# E22_TTL_RS232_v0_2_-20200615.net
KiCad netlist of a schematic drawn in Altium Designer
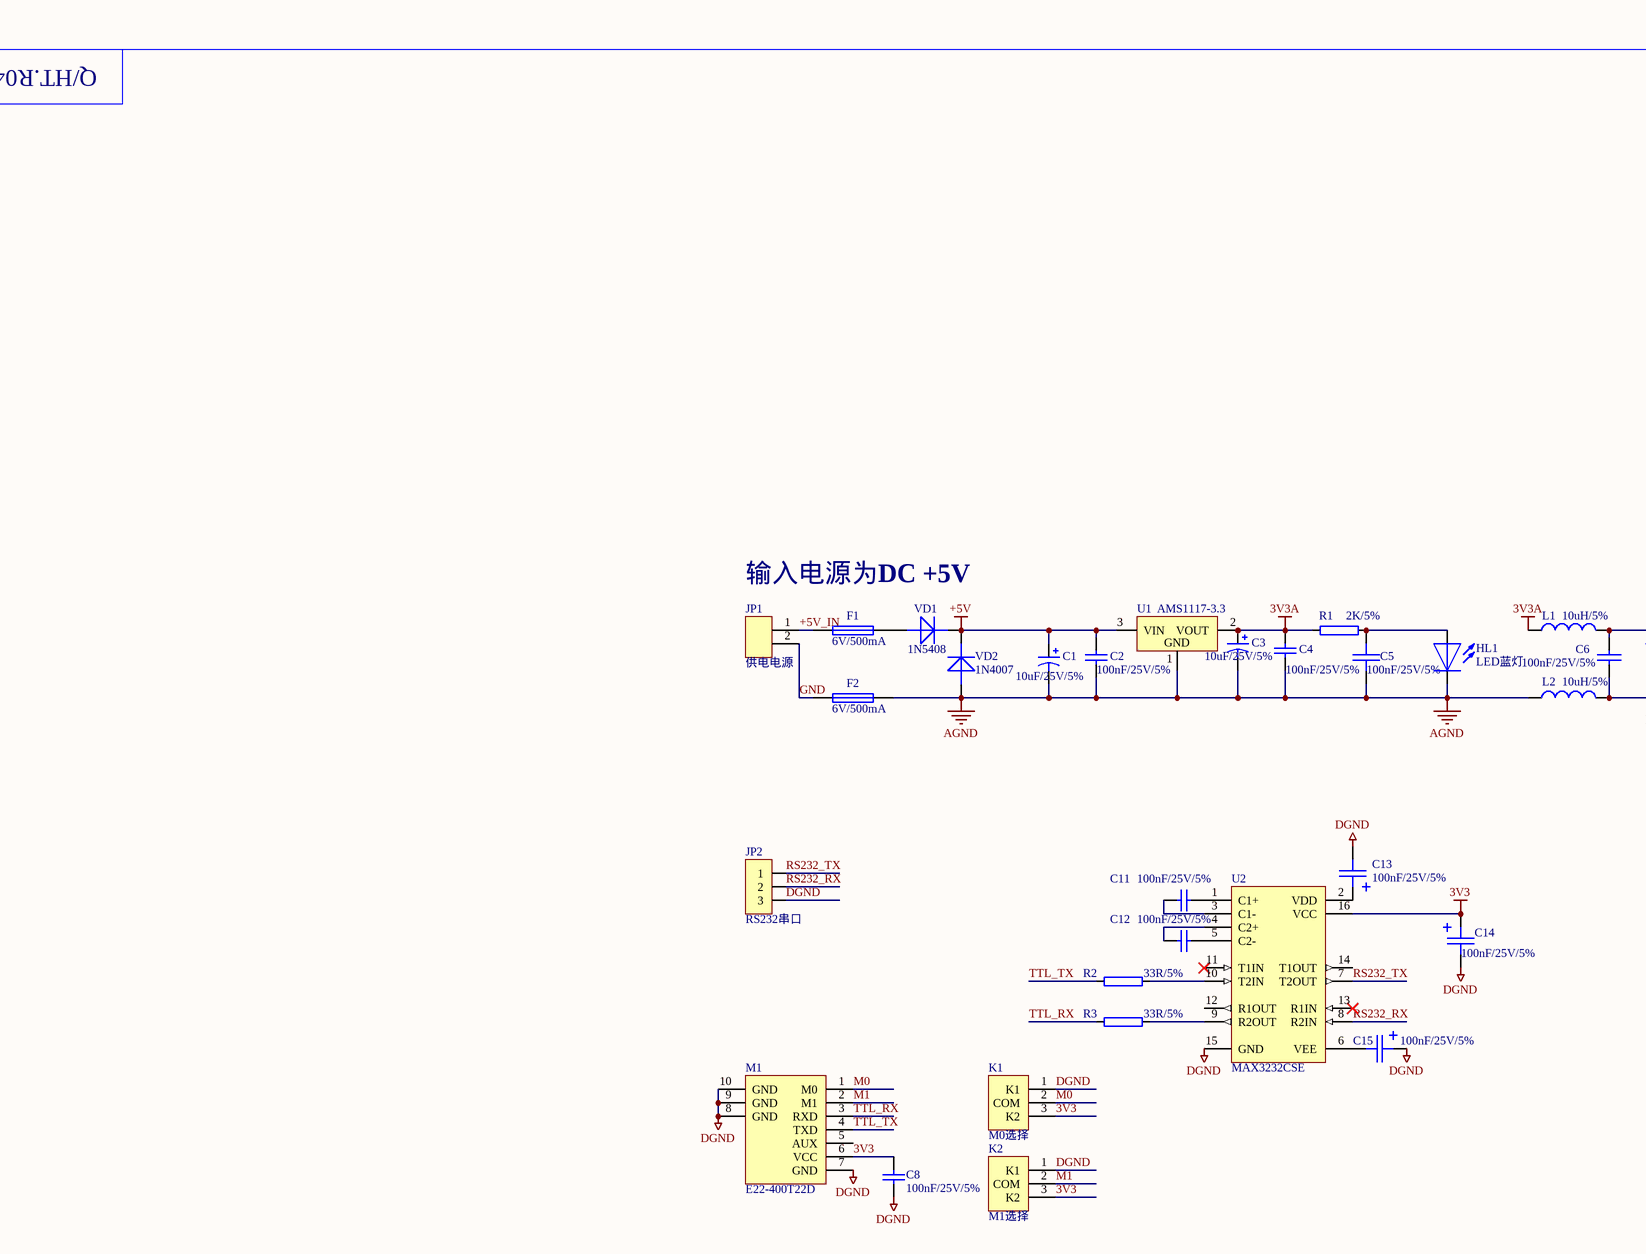
[diagram p0: E22_TTL_RS232(v0.2)-20200615.SchDoc, top left]
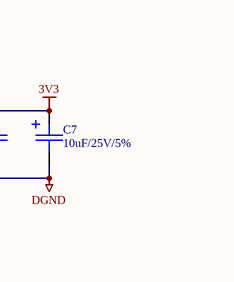
[diagram p1: E22_TTL_RS232(v0.2)-20200615.SchDoc, top right]
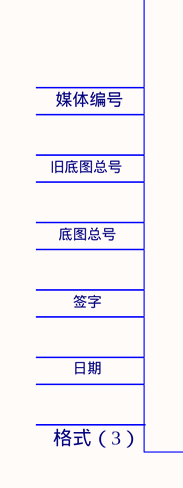
[diagram p2: E22_TTL_RS232(v0.2)-20200615.SchDoc, bottom left]
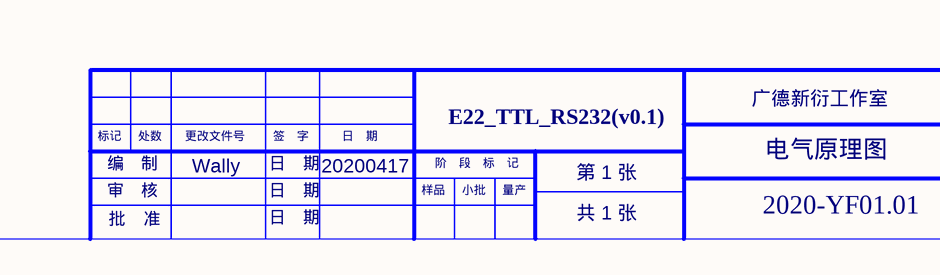
[diagram p3: E22_TTL_RS232(v0.2)-20200615.SchDoc, bottom right]

(export (version "E")
  (design (tool "Eeschema 10.0.6"))
  (components
    (comp (ref "C1")
      (value "10uF/25V/5%")
      (footprint "C1206-1")
      (description "钽电容")
      (fields (field (name "PUBLISHER") "Altium Limited"))
      (libsource (lib "Miscellaneous Devices") (part "Cap Pol1"))
    )
    (comp (ref "C2")
      (value "100nF/25V/5%")
      (footprint "C0603")
      (description "电容")
      (fields (field (name "PUBLISHER") "Altium Limited"))
      (libsource (lib "Miscellaneous Devices") (part "Cap"))
    )
    (comp (ref "C3")
      (value "10uF/25V/5%")
      (footprint "C1206-1")
      (description "钽电容")
      (fields (field (name "PUBLISHER") "Altium Limited"))
      (libsource (lib "Miscellaneous Devices") (part "Cap Pol1"))
    )
    (comp (ref "C4")
      (value "100nF/25V/5%")
      (footprint "C0603")
      (description "电容")
      (fields (field (name "PUBLISHER") "Altium Limited"))
      (libsource (lib "Miscellaneous Devices") (part "Cap"))
    )
    (comp (ref "C5")
      (value "100nF/25V/5%")
      (footprint "C0603")
      (description "电容")
      (libsource (lib "*") (part "CAP"))
    )
    (comp (ref "C6")
      (value "100nF/25V/5%")
      (footprint "C0603")
      (description "电容")
      (libsource (lib "") (part "CAP_1"))
    )
    (comp (ref "C7")
      (value "10uF/25V/5%")
      (footprint "C1206-1")
      (description "钽电容")
      (libsource (lib "*") (part "ELECTRO1"))
    )
    (comp (ref "C8")
      (value "100nF/25V/5%")
      (footprint "C0603")
      (description "电容")
      (libsource (lib "*") (part "CAP-SMD"))
    )
    (comp (ref "C11")
      (value "100nF/25V/5%")
      (footprint "C0603")
      (description "电容")
      (libsource (lib "*") (part "CAP-SMD"))
    )
    (comp (ref "C12")
      (value "100nF/25V/5%")
      (footprint "C0603")
      (description "电容")
      (libsource (lib "*") (part "CAP-SMD"))
    )
    (comp (ref "C13")
      (value "100nF/25V/5%")
      (footprint "C1206-1")
      (description "钽电容")
      (libsource (lib "*") (part "ELECTRO1"))
    )
    (comp (ref "C14")
      (value "100nF/25V/5%")
      (footprint "C1206-1")
      (description "钽电容")
      (libsource (lib "*") (part "ELECTRO1"))
    )
    (comp (ref "C15")
      (value "100nF/25V/5%")
      (footprint "C1206-1")
      (description "钽电容")
      (libsource (lib "*") (part "ELECTRO1"))
    )
    (comp (ref "F1")
      (value "6V/500mA")
      (footprint "F1812")
      (description "自恢复保险丝")
      (libsource (lib "wypPCB_Lib") (part "保险丝"))
    )
    (comp (ref "F2")
      (value "6V/500mA")
      (footprint "F1812")
      (description "自恢复保险丝")
      (libsource (lib "wypPCB_Lib") (part "保险丝"))
    )
    (comp (ref "HL1")
      (value "LED蓝灯")
      (footprint "LED0603")
      (description "发光二极管")
      (libsource (lib "wypPCB_Lib") (part "发光二极管"))
    )
    (comp (ref "JP1")
      (value "供电电源")
      (footprint "XH2.54-LI-2P")
      (description "XH2.54-2P/PH2.0-2P插座")
      (libsource (lib "wypPCB_Lib") (part "XH2.54-2P/PH2.0-2P"))
    )
    (comp (ref "JP2")
      (value "RS232串口")
      (footprint "PH2.0-LI-3P")
      (description "PH2.0-3P直插插座")
      (libsource (lib "wypPCB_Lib") (part "XH2.54-3P/PH2.0-3P"))
    )
    (comp (ref "K1")
      (value "M0选择")
      (footprint "SK-12D07")
      (description "SK-12D07：3脚2档小型拨动开关")
      (libsource (lib "wypPCB_Lib") (part "SK-12D07"))
    )
    (comp (ref "K2")
      (value "M1选择")
      (footprint "SK-12D07")
      (description "SK-12D07：3脚2档小型拨动开关")
      (libsource (lib "wypPCB_Lib") (part "SK-12D07"))
    )
    (comp (ref "L1")
      (value "10uH/5%")
      (footprint "L0603")
      (description "电感")
      (libsource (lib "wypPCB_Lib") (part "电感"))
    )
    (comp (ref "L2")
      (value "10uH/5%")
      (footprint "L0603")
      (description "电感")
      (libsource (lib "wypPCB_Lib") (part "电感"))
    )
    (comp (ref "M1")
      (value "E22-400T22D")
      (footprint "E22-400T22D")
      (description "E22-400T22D LoRa模块")
      (libsource (lib "wypPCB_Lib") (part "E22-400T22D"))
    )
    (comp (ref "R1")
      (value "2K/5%")
      (footprint "R0603")
      (description "电阻")
      (libsource (lib "*") (part "RES2"))
    )
    (comp (ref "R2")
      (value "33R/5%")
      (footprint "R0603")
      (description "电阻")
      (libsource (lib "*") (part "RES2"))
    )
    (comp (ref "R3")
      (value "33R/5%")
      (footprint "R0603")
      (description "电阻")
      (libsource (lib "*") (part "RES2"))
    )
    (comp (ref "U1")
      (value "AMS1117-3.3")
      (footprint "SOT230P700X180-4N")
      (description "U_AMS1117稳压芯片")
      (libsource (lib "wypPCB_Lib") (part "U_AMS1117"))
    )
    (comp (ref "U2")
      (value "MAX3232CSE")
      (footprint "NSO16_M")
      (description "+5V Powered, Multi-Channel RS-232 Driver/Receiver")
      (fields (field (name "PUBLISHER") "Altium Limited"))
      (libsource (lib "Maxim Communication Transceiver") (part "MAX232CSE"))
    )
    (comp (ref "VD1")
      (value "1N5408")
      (footprint "SMA_DO-214AC")
      (description "开关二极管")
      (libsource (lib "wypPCB_Lib") (part "开关二极管"))
    )
    (comp (ref "VD2")
      (value "1N4007")
      (footprint "SMA_DO-214AC")
      (description "开关二极管")
      (libsource (lib "wypPCB_Lib") (part "开关二极管"))
    )
  )
  (nets
    (net (code "1") (name "+5V") (class "Default")
      (node (ref "C1") (pin "1") (pinfunction "1_1") (pintype "passive"))
      (node (ref "C2") (pin "2") (pinfunction "2_2") (pintype "passive"))
      (node (ref "U1") (pin "3") (pinfunction "VIN_3") (pintype "passive"))
      (node (ref "VD1") (pin "K") (pintype "passive"))
      (node (ref "VD2") (pin "K") (pintype "passive"))
    )
    (net (code "2") (name "/+5V_IN") (class "Default")
      (node (ref "F1") (pin "1") (pintype "passive"))
      (node (ref "JP1") (pin "1") (pintype "passive"))
    )
    (net (code "3") (name "/GND") (class "Default")
      (node (ref "F2") (pin "1") (pintype "passive"))
      (node (ref "JP1") (pin "2") (pintype "passive"))
    )
    (net (code "4") (name "/M0") (class "Default")
      (node (ref "K1") (pin "2") (pinfunction "COM_2") (pintype "passive"))
      (node (ref "M1") (pin "1") (pinfunction "M0_1") (pintype "passive"))
    )
    (net (code "5") (name "/M1") (class "Default")
      (node (ref "K2") (pin "2") (pinfunction "COM_2") (pintype "passive"))
      (node (ref "M1") (pin "2") (pinfunction "M1_2") (pintype "passive"))
    )
    (net (code "6") (name "/RS232_RX") (class "Default")
      (node (ref "JP2") (pin "2") (pinfunction "2_2") (pintype "passive"))
      (node (ref "U2") (pin "8") (pinfunction "R2IN_8") (pintype "input"))
    )
    (net (code "7") (name "/RS232_TX") (class "Default")
      (node (ref "JP2") (pin "1") (pinfunction "1_1") (pintype "passive"))
      (node (ref "U2") (pin "7") (pinfunction "T2OUT_7") (pintype "output"))
    )
    (net (code "8") (name "/TTL_RX") (class "Default")
      (node (ref "M1") (pin "3") (pinfunction "RXD_3") (pintype "passive"))
      (node (ref "R3") (pin "2") (pintype "passive"))
    )
    (net (code "9") (name "/TTL_TX") (class "Default")
      (node (ref "M1") (pin "4") (pinfunction "TXD_4") (pintype "passive"))
      (node (ref "R2") (pin "2") (pintype "passive"))
    )
    (net (code "10") (name "3V3") (class "Default")
      (node (ref "C14") (pin "1") (pintype "passive"))
      (node (ref "C6") (pin "2") (pintype "passive"))
      (node (ref "C7") (pin "1") (pintype "passive"))
      (node (ref "C8") (pin "2") (pintype "passive"))
      (node (ref "K1") (pin "3") (pinfunction "K2_3") (pintype "passive"))
      (node (ref "K2") (pin "3") (pinfunction "K2_3") (pintype "passive"))
      (node (ref "L1") (pin "2") (pinfunction "2_2") (pintype "passive"))
      (node (ref "M1") (pin "6") (pinfunction "VCC_6") (pintype "passive"))
      (node (ref "U2") (pin "16") (pinfunction "VCC_16") (pintype "power_in"))
    )
    (net (code "11") (name "3V3A") (class "Default")
      (node (ref "C3") (pin "1") (pinfunction "1_1") (pintype "passive"))
      (node (ref "C4") (pin "2") (pinfunction "2_2") (pintype "passive"))
      (node (ref "L1") (pin "1") (pinfunction "1_1") (pintype "passive"))
      (node (ref "R1") (pin "1") (pintype "passive"))
      (node (ref "U1") (pin "2") (pinfunction "VOUT_2") (pintype "passive"))
    )
    (net (code "12") (name "AGND") (class "Default")
      (node (ref "C1") (pin "2") (pinfunction "2_2") (pintype "passive"))
      (node (ref "C2") (pin "1") (pinfunction "1_1") (pintype "passive"))
      (node (ref "C3") (pin "2") (pinfunction "2_2") (pintype "passive"))
      (node (ref "C4") (pin "1") (pinfunction "1_1") (pintype "passive"))
      (node (ref "C5") (pin "2") (pintype "passive"))
      (node (ref "F2") (pin "2") (pintype "passive"))
      (node (ref "HL1") (pin "K") (pintype "passive"))
      (node (ref "L2") (pin "1") (pinfunction "1_1") (pintype "passive"))
      (node (ref "U1") (pin "1") (pinfunction "GND_1") (pintype "passive"))
      (node (ref "VD2") (pin "A") (pintype "passive"))
    )
    (net (code "13") (name "DGND") (class "Default")
      (node (ref "C13") (pin "2") (pintype "passive"))
      (node (ref "C14") (pin "2") (pintype "passive"))
      (node (ref "C15") (pin "1") (pintype "passive"))
      (node (ref "C6") (pin "1") (pintype "passive"))
      (node (ref "C7") (pin "2") (pintype "passive"))
      (node (ref "C8") (pin "1") (pintype "passive"))
      (node (ref "JP2") (pin "3") (pinfunction "3_3") (pintype "passive"))
      (node (ref "K1") (pin "1") (pinfunction "K1_1") (pintype "passive"))
      (node (ref "K2") (pin "1") (pinfunction "K1_1") (pintype "passive"))
      (node (ref "L2") (pin "2") (pinfunction "2_2") (pintype "passive"))
      (node (ref "M1") (pin "10") (pinfunction "GND_10") (pintype "passive"))
      (node (ref "M1") (pin "7") (pinfunction "GND_7") (pintype "passive"))
      (node (ref "M1") (pin "8") (pinfunction "GND_8") (pintype "passive"))
      (node (ref "M1") (pin "9") (pinfunction "GND_9") (pintype "passive"))
      (node (ref "U2") (pin "15") (pinfunction "GND_15") (pintype "power_in"))
    )
    (net (code "14") (name "Net-(C5-Pad1)") (class "Default")
      (node (ref "C5") (pin "1") (pintype "passive"))
      (node (ref "HL1") (pin "A") (pintype "passive"))
      (node (ref "R1") (pin "2") (pintype "passive"))
    )
    (net (code "15") (name "Net-(F1-Pad2)") (class "Default")
      (node (ref "F1") (pin "2") (pintype "passive"))
      (node (ref "VD1") (pin "A") (pintype "passive"))
    )
    (net (code "16") (name "Net-(U2-C1+)") (class "Default")
      (node (ref "C11") (pin "2") (pintype "passive"))
      (node (ref "U2") (pin "1") (pinfunction "C1+_1") (pintype "passive"))
    )
    (net (code "17") (name "Net-(U2-C1-)") (class "Default")
      (node (ref "C11") (pin "1") (pintype "passive"))
      (node (ref "U2") (pin "3") (pinfunction "C1-_3") (pintype "passive"))
    )
    (net (code "18") (name "Net-(U2-C2+)") (class "Default")
      (node (ref "C12") (pin "1") (pintype "passive"))
      (node (ref "U2") (pin "4") (pinfunction "C2+_4") (pintype "passive"))
    )
    (net (code "19") (name "Net-(U2-C2-)") (class "Default")
      (node (ref "C12") (pin "2") (pintype "passive"))
      (node (ref "U2") (pin "5") (pinfunction "C2-_5") (pintype "passive"))
    )
    (net (code "20") (name "Net-(U2-R2OUT)") (class "Default")
      (node (ref "R3") (pin "1") (pintype "passive"))
      (node (ref "U2") (pin "9") (pinfunction "R2OUT_9") (pintype "output"))
    )
    (net (code "21") (name "Net-(U2-T2IN)") (class "Default")
      (node (ref "R2") (pin "1") (pintype "passive"))
      (node (ref "U2") (pin "10") (pinfunction "T2IN_10") (pintype "input"))
    )
    (net (code "22") (name "Net-(U2-VDD)") (class "Default")
      (node (ref "C13") (pin "1") (pintype "passive"))
      (node (ref "U2") (pin "2") (pinfunction "VDD_2") (pintype "power_in"))
    )
    (net (code "23") (name "Net-(U2-VEE)") (class "Default")
      (node (ref "C15") (pin "2") (pintype "passive"))
      (node (ref "U2") (pin "6") (pinfunction "VEE_6") (pintype "power_in"))
    )
    (net (code "24") (name "unconnected-(M1-AUX-Pad5)") (class "Default")
      (node (ref "M1") (pin "5") (pinfunction "AUX_5") (pintype "passive"))
    )
    (net (code "25") (name "unconnected-(U2-R1IN-Pad13)") (class "Default")
      (node (ref "U2") (pin "13") (pinfunction "R1IN_13") (pintype "input+no_connect"))
    )
    (net (code "26") (name "unconnected-(U2-R1OUT-Pad12)") (class "Default")
      (node (ref "U2") (pin "12") (pinfunction "R1OUT_12") (pintype "output"))
    )
    (net (code "27") (name "unconnected-(U2-T1IN-Pad11)") (class "Default")
      (node (ref "U2") (pin "11") (pinfunction "T1IN_11") (pintype "input+no_connect"))
    )
    (net (code "28") (name "unconnected-(U2-T1OUT-Pad14)") (class "Default")
      (node (ref "U2") (pin "14") (pinfunction "T1OUT_14") (pintype "output"))
    )
  )
)
